# Dual_USB-A.net
KiCad netlist of a schematic drawn in Altium Designer
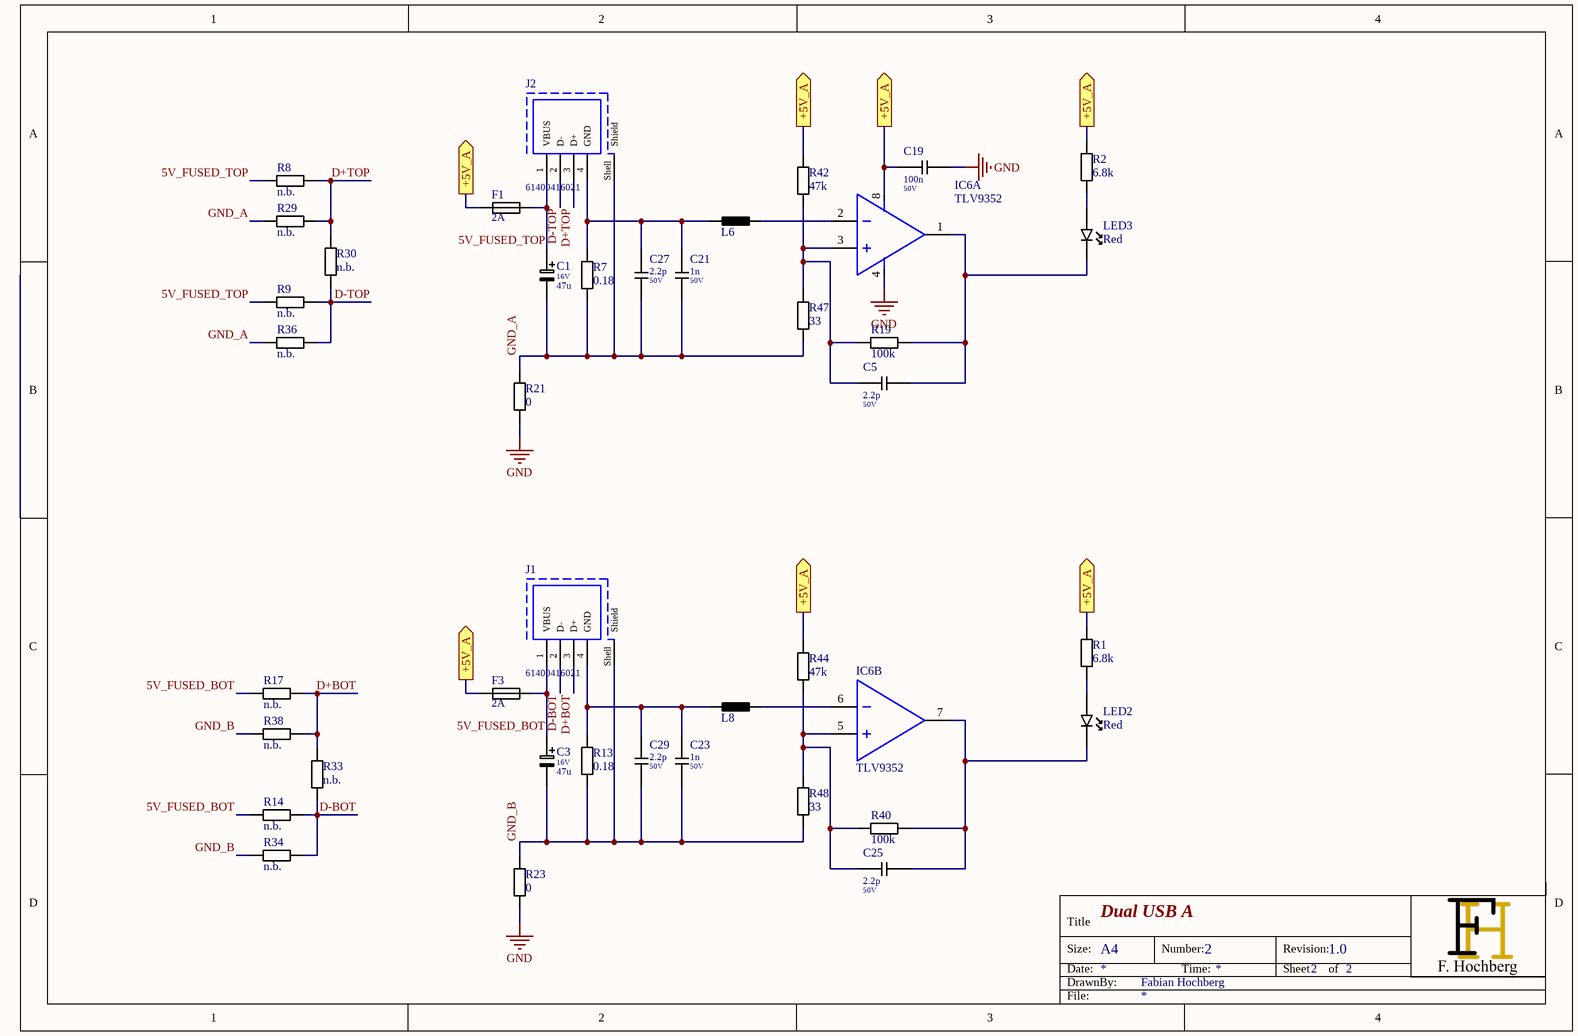
[diagram p0: Dual_USB-A.SchDoc]

(export (version "E")
  (design (tool "Eeschema 10.0.6"))
  (components
    (comp (ref "C1")
      (value "47u")
      (footprint "CAPAE_5x5.4")
      (description "Elko")
      (fields (field (name "VOLTAGE") "16V") (field (name "Comment") "47u_16V"))
      (libsource (lib "Passives_FH") (part "C POL"))
    )
    (comp (ref "C3")
      (value "47u")
      (footprint "CAPAE_5x5.4")
      (description "Elko")
      (fields (field (name "VOLTAGE") "16V") (field (name "Comment") "47u_16V"))
      (libsource (lib "Passives_FH") (part "C POL"))
    )
    (comp (ref "C5")
      (value "2.2p")
      (footprint "0603_C")
      (description "Keramikkondensator")
      (fields (field (name "VOLTAGE") "50V") (field (name "Comment") "2.2p_50V"))
      (libsource (lib "Passives_FH") (part "C"))
    )
    (comp (ref "C19")
      (value "100n")
      (footprint "0603_C")
      (description "Keramikkondensator")
      (fields (field (name "VOLTAGE") "50V") (field (name "Comment") "100n_50V"))
      (libsource (lib "Passives_FH") (part "C"))
    )
    (comp (ref "C21")
      (value "1n")
      (footprint "0603_C")
      (description "Keramikkondensator")
      (fields (field (name "VOLTAGE") "50V") (field (name "Comment") "1n_50V"))
      (libsource (lib "Passives_FH") (part "C"))
    )
    (comp (ref "C23")
      (value "1n")
      (footprint "0603_C")
      (description "Keramikkondensator")
      (fields (field (name "VOLTAGE") "50V") (field (name "Comment") "1n_50V"))
      (libsource (lib "Passives_FH") (part "C"))
    )
    (comp (ref "C25")
      (value "2.2p")
      (footprint "0603_C")
      (description "Keramikkondensator")
      (fields (field (name "VOLTAGE") "50V") (field (name "Comment") "2.2p_50V"))
      (libsource (lib "Passives_FH") (part "C"))
    )
    (comp (ref "C27")
      (value "2.2p")
      (footprint "0603_C")
      (description "Keramikkondensator")
      (fields (field (name "VOLTAGE") "50V") (field (name "Comment") "2.2p_50V"))
      (libsource (lib "Passives_FH") (part "C"))
    )
    (comp (ref "C29")
      (value "2.2p")
      (footprint "0603_C")
      (description "Keramikkondensator")
      (fields (field (name "VOLTAGE") "50V") (field (name "Comment") "2.2p_50V"))
      (libsource (lib "Passives_FH") (part "C"))
    )
    (comp (ref "F1")
      (value "2A")
      (footprint "0603_Fuse")
      (description "Fuse")
      (libsource (lib "Passives_FH") (part "Fuse"))
    )
    (comp (ref "F3")
      (value "2A")
      (footprint "0603_Fuse")
      (description "Fuse")
      (libsource (lib "Passives_FH") (part "Fuse"))
    )
    (comp (ref "IC6")
      (value "TLV9352")
      (footprint "SOT23-8")
      (description "OP / Comparator")
      (libsource (lib "ICs_Analog_FH") (part "Dual OP Amp"))
    )
    (comp (ref "J1")
      (value "61400416021")
      (footprint "61400416021")
      (description "USB 2.0 Type A Receptacle WR-COM, Horizontal, THT")
      (fields (field (name "MANUFACTURER") "Wurth Elektronik") (field (name "PUBLISHER") "WurthElektronik"))
      (libsource (lib "Altium Content Vault") (part "WE-USB-4-1SHLD"))
    )
    (comp (ref "J2")
      (value "61400416021")
      (footprint "61400416021")
      (description "USB 2.0 Type A Receptacle WR-COM, Horizontal, THT")
      (fields (field (name "MANUFACTURER") "Wurth Elektronik") (field (name "PUBLISHER") "WurthElektronik"))
      (libsource (lib "Altium Content Vault") (part "WE-USB-4-1SHLD"))
    )
    (comp (ref "L6")
      (value "100 Ohm @ 100MHz")
      (footprint "0603_L")
      (description "0,15 Ohm 1A max\r\n100 Ohm @ 100MHz")
      (libsource (lib "Passives_FH") (part "L"))
    )
    (comp (ref "L8")
      (value "100 Ohm @ 100MHz")
      (footprint "0603_L")
      (description "0,15 Ohm 1A max\r\n100 Ohm @ 100MHz")
      (libsource (lib "Passives_FH") (part "L"))
    )
    (comp (ref "LED2")
      (value "Red")
      (footprint "0603_LED")
      (description "LED")
      (fields (field (name "COLOR") "Red"))
      (libsource (lib "Optical_FH") (part "LED"))
    )
    (comp (ref "LED3")
      (value "Red")
      (footprint "0603_LED")
      (description "LED")
      (fields (field (name "COLOR") "Red"))
      (libsource (lib "Optical_FH") (part "LED"))
    )
    (comp (ref "R1") (value "6.8k") (footprint "0603_R") (description "R") (libsource (lib "") (part "R_1")))
    (comp (ref "R2") (value "6.8k") (footprint "0603_R") (description "R") (libsource (lib "") (part "R_1")))
    (comp (ref "R7") (value "0.18") (footprint "2512_R") (description "R") (libsource (lib "") (part "R_1")))
    (comp (ref "R8")
      (value "n.b.")
      (footprint "0603_R")
      (description "R")
      (libsource (lib "Passives_FH") (part "R"))
    )
    (comp (ref "R9")
      (value "n.b.")
      (footprint "0603_R")
      (description "R")
      (libsource (lib "Passives_FH") (part "R"))
    )
    (comp (ref "R13") (value "0.18") (footprint "2512_R") (description "R") (libsource (lib "") (part "R_1")))
    (comp (ref "R14")
      (value "n.b.")
      (footprint "0603_R")
      (description "R")
      (libsource (lib "Passives_FH") (part "R"))
    )
    (comp (ref "R17")
      (value "n.b.")
      (footprint "0603_R")
      (description "R")
      (libsource (lib "Passives_FH") (part "R"))
    )
    (comp (ref "R19") (value "100k") (footprint "0603_R") (description "R") (libsource (lib "") (part "R_2")))
    (comp (ref "R21")
      (value "0")
      (footprint "0603_R")
      (description "R")
      (libsource (lib "Passives_FH") (part "R"))
    )
    (comp (ref "R23")
      (value "0")
      (footprint "0603_R")
      (description "R")
      (libsource (lib "Passives_FH") (part "R"))
    )
    (comp (ref "R29")
      (value "n.b.")
      (footprint "0603_R")
      (description "R")
      (libsource (lib "Passives_FH") (part "R"))
    )
    (comp (ref "R30") (value "n.b.") (footprint "0603_R") (description "R") (libsource (lib "") (part "R_3")))
    (comp (ref "R33") (value "n.b.") (footprint "0603_R") (description "R") (libsource (lib "") (part "R_3")))
    (comp (ref "R34")
      (value "n.b.")
      (footprint "0603_R")
      (description "R")
      (libsource (lib "Passives_FH") (part "R"))
    )
    (comp (ref "R36")
      (value "n.b.")
      (footprint "0603_R")
      (description "R")
      (libsource (lib "Passives_FH") (part "R"))
    )
    (comp (ref "R38")
      (value "n.b.")
      (footprint "0603_R")
      (description "R")
      (libsource (lib "Passives_FH") (part "R"))
    )
    (comp (ref "R40") (value "100k") (footprint "0603_R") (description "R") (libsource (lib "") (part "R_2")))
    (comp (ref "R42") (value "47k") (footprint "0603_R") (description "R") (libsource (lib "") (part "R_1")))
    (comp (ref "R44") (value "47k") (footprint "0603_R") (description "R") (libsource (lib "") (part "R_1")))
    (comp (ref "R47") (value "33") (footprint "0603_R") (description "R") (libsource (lib "") (part "R_1")))
    (comp (ref "R48") (value "33") (footprint "0603_R") (description "R") (libsource (lib "") (part "R_1")))
  )
  (nets
    (net (code "1") (name "/+5V_A") (class "Default")
      (node (ref "C19") (pin "2") (pinfunction "2_2") (pintype "passive"))
      (node (ref "F1") (pin "2") (pinfunction "2_2") (pintype "passive"))
      (node (ref "F3") (pin "2") (pinfunction "2_2") (pintype "passive"))
      (node (ref "IC6") (pin "8") (pinfunction "V15_8") (pintype "passive"))
      (node (ref "R1") (pin "2") (pinfunction "2_2") (pintype "passive"))
      (node (ref "R2") (pin "2") (pinfunction "2_2") (pintype "passive"))
      (node (ref "R42") (pin "2") (pinfunction "2_2") (pintype "passive"))
      (node (ref "R44") (pin "2") (pinfunction "2_2") (pintype "passive"))
    )
    (net (code "2") (name "/5V_FUSED_BOT") (class "Default")
      (node (ref "C3") (pin "1") (pinfunction "1_1") (pintype "passive"))
      (node (ref "F3") (pin "1") (pinfunction "1_1") (pintype "passive"))
      (node (ref "J1") (pin "1") (pinfunction "VBUS_1") (pintype "passive"))
      (node (ref "R14") (pin "2") (pinfunction "2_2") (pintype "passive"))
      (node (ref "R17") (pin "2") (pinfunction "2_2") (pintype "passive"))
    )
    (net (code "3") (name "/5V_FUSED_TOP") (class "Default")
      (node (ref "C1") (pin "1") (pinfunction "1_1") (pintype "passive"))
      (node (ref "F1") (pin "1") (pinfunction "1_1") (pintype "passive"))
      (node (ref "J2") (pin "1") (pinfunction "VBUS_1") (pintype "passive"))
      (node (ref "R8") (pin "2") (pinfunction "2_2") (pintype "passive"))
      (node (ref "R9") (pin "2") (pinfunction "2_2") (pintype "passive"))
    )
    (net (code "4") (name "/D+BOT") (class "Default")
      (node (ref "J1") (pin "3") (pinfunction "D+_3") (pintype "passive"))
      (node (ref "R17") (pin "1") (pinfunction "1_1") (pintype "passive"))
      (node (ref "R33") (pin "1") (pinfunction "1_1") (pintype "passive"))
      (node (ref "R38") (pin "1") (pinfunction "1_1") (pintype "passive"))
    )
    (net (code "5") (name "/D+TOP") (class "Default")
      (node (ref "J2") (pin "3") (pinfunction "D+_3") (pintype "passive"))
      (node (ref "R29") (pin "1") (pinfunction "1_1") (pintype "passive"))
      (node (ref "R30") (pin "1") (pinfunction "1_1") (pintype "passive"))
      (node (ref "R8") (pin "1") (pinfunction "1_1") (pintype "passive"))
    )
    (net (code "6") (name "/D-BOT") (class "Default")
      (node (ref "J1") (pin "2") (pinfunction "D-_2") (pintype "passive"))
      (node (ref "R14") (pin "1") (pinfunction "1_1") (pintype "passive"))
      (node (ref "R33") (pin "2") (pinfunction "2_2") (pintype "passive"))
      (node (ref "R34") (pin "1") (pinfunction "1_1") (pintype "passive"))
    )
    (net (code "7") (name "/D-TOP") (class "Default")
      (node (ref "J2") (pin "2") (pinfunction "D-_2") (pintype "passive"))
      (node (ref "R30") (pin "2") (pinfunction "2_2") (pintype "passive"))
      (node (ref "R36") (pin "1") (pinfunction "1_1") (pintype "passive"))
      (node (ref "R9") (pin "1") (pinfunction "1_1") (pintype "passive"))
    )
    (net (code "8") (name "/GND_A") (class "Default")
      (node (ref "C1") (pin "2") (pinfunction "2_2") (pintype "passive"))
      (node (ref "C21") (pin "2") (pinfunction "2_2") (pintype "passive"))
      (node (ref "C27") (pin "2") (pinfunction "2_2") (pintype "passive"))
      (node (ref "J2") (pin "Shell") (pinfunction "Shield_Shell") (pintype "passive"))
      (node (ref "R21") (pin "1") (pinfunction "1_1") (pintype "passive"))
      (node (ref "R29") (pin "2") (pinfunction "2_2") (pintype "passive"))
      (node (ref "R36") (pin "2") (pinfunction "2_2") (pintype "passive"))
      (node (ref "R47") (pin "1") (pinfunction "1_1") (pintype "passive"))
      (node (ref "R7") (pin "1") (pinfunction "1_1") (pintype "passive"))
    )
    (net (code "9") (name "/GND_B") (class "Default")
      (node (ref "C23") (pin "2") (pinfunction "2_2") (pintype "passive"))
      (node (ref "C29") (pin "2") (pinfunction "2_2") (pintype "passive"))
      (node (ref "C3") (pin "2") (pinfunction "2_2") (pintype "passive"))
      (node (ref "J1") (pin "Shell") (pinfunction "Shield_Shell") (pintype "passive"))
      (node (ref "R13") (pin "1") (pinfunction "1_1") (pintype "passive"))
      (node (ref "R23") (pin "1") (pinfunction "1_1") (pintype "passive"))
      (node (ref "R34") (pin "2") (pinfunction "2_2") (pintype "passive"))
      (node (ref "R38") (pin "2") (pinfunction "2_2") (pintype "passive"))
      (node (ref "R48") (pin "1") (pinfunction "1_1") (pintype "passive"))
    )
    (net (code "10") (name "GND") (class "Default")
      (node (ref "C19") (pin "1") (pinfunction "1_1") (pintype "passive"))
      (node (ref "IC6") (pin "4") (pinfunction "GND_4") (pintype "passive"))
      (node (ref "R21") (pin "2") (pinfunction "2_2") (pintype "passive"))
      (node (ref "R23") (pin "2") (pinfunction "2_2") (pintype "passive"))
    )
    (net (code "11") (name "Net-(C5-Pad2)") (class "Default")
      (node (ref "C5") (pin "2") (pinfunction "2_2") (pintype "passive"))
      (node (ref "IC6") (pin "3") (pintype "passive"))
      (node (ref "R19") (pin "1") (pinfunction "1_1") (pintype "passive"))
      (node (ref "R42") (pin "1") (pinfunction "1_1") (pintype "passive"))
      (node (ref "R47") (pin "2") (pinfunction "2_2") (pintype "passive"))
    )
    (net (code "12") (name "Net-(C25-Pad2)") (class "Default")
      (node (ref "C25") (pin "2") (pinfunction "2_2") (pintype "passive"))
      (node (ref "IC6") (pin "5") (pintype "passive"))
      (node (ref "R40") (pin "1") (pinfunction "1_1") (pintype "passive"))
      (node (ref "R44") (pin "1") (pinfunction "1_1") (pintype "passive"))
      (node (ref "R48") (pin "2") (pinfunction "2_2") (pintype "passive"))
    )
    (net (code "13") (name "Net-(IC6-Pad2)") (class "Default")
      (node (ref "IC6") (pin "2") (pintype "passive"))
      (node (ref "L6") (pin "2") (pinfunction "2_2") (pintype "passive"))
    )
    (net (code "14") (name "Net-(IC6-Pad6)") (class "Default")
      (node (ref "IC6") (pin "6") (pintype "passive"))
      (node (ref "L8") (pin "2") (pinfunction "2_2") (pintype "passive"))
    )
    (net (code "15") (name "Net-(J1-GND)") (class "Default")
      (node (ref "C23") (pin "1") (pinfunction "1_1") (pintype "passive"))
      (node (ref "C29") (pin "1") (pinfunction "1_1") (pintype "passive"))
      (node (ref "J1") (pin "4") (pinfunction "GND_4") (pintype "passive"))
      (node (ref "L8") (pin "1") (pinfunction "1_1") (pintype "passive"))
      (node (ref "R13") (pin "2") (pinfunction "2_2") (pintype "passive"))
    )
    (net (code "16") (name "Net-(J2-GND)") (class "Default")
      (node (ref "C21") (pin "1") (pinfunction "1_1") (pintype "passive"))
      (node (ref "C27") (pin "1") (pinfunction "1_1") (pintype "passive"))
      (node (ref "J2") (pin "4") (pinfunction "GND_4") (pintype "passive"))
      (node (ref "L6") (pin "1") (pinfunction "1_1") (pintype "passive"))
      (node (ref "R7") (pin "2") (pinfunction "2_2") (pintype "passive"))
    )
    (net (code "17") (name "Net-(LED2-A)") (class "Default")
      (node (ref "LED2") (pin "2") (pinfunction "A_2") (pintype "passive"))
      (node (ref "R1") (pin "1") (pinfunction "1_1") (pintype "passive"))
    )
    (net (code "18") (name "Net-(LED2-K)") (class "Default")
      (node (ref "C25") (pin "1") (pinfunction "1_1") (pintype "passive"))
      (node (ref "IC6") (pin "7") (pintype "passive"))
      (node (ref "LED2") (pin "1") (pinfunction "K_1") (pintype "passive"))
      (node (ref "R40") (pin "2") (pinfunction "2_2") (pintype "passive"))
    )
    (net (code "19") (name "Net-(LED3-A)") (class "Default")
      (node (ref "LED3") (pin "2") (pinfunction "A_2") (pintype "passive"))
      (node (ref "R2") (pin "1") (pinfunction "1_1") (pintype "passive"))
    )
    (net (code "20") (name "Net-(LED3-K)") (class "Default")
      (node (ref "C5") (pin "1") (pinfunction "1_1") (pintype "passive"))
      (node (ref "IC6") (pin "1") (pintype "passive"))
      (node (ref "LED3") (pin "1") (pinfunction "K_1") (pintype "passive"))
      (node (ref "R19") (pin "2") (pinfunction "2_2") (pintype "passive"))
    )
  )
)
